# ESP01_ManualPushbutton.net
KiCad netlist of a schematic drawn in EAGLE
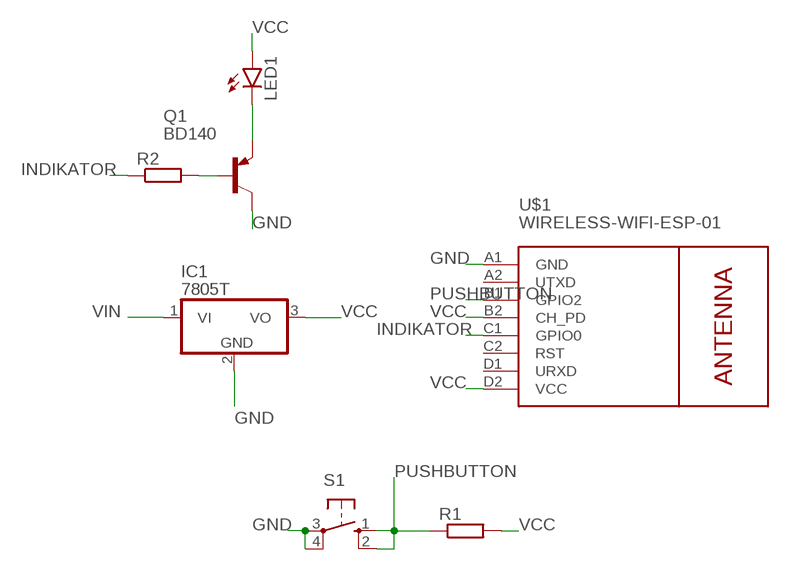
[diagram p0: schematic, sheet 1]

(export (version "E")
  (design (tool "Eeschema 10.0.6"))
  (components
    (comp (ref "IC1")
      (value "7805T")
      (footprint "eagle-import:TO220H")
      (libsource (lib "eagle-import") (part "78T05"))
    )
    (comp (ref "LED1")
      (value "LED5MM")
      (footprint "eagle-import:LED5MM")
      (libsource (lib "eagle-import") (part "LED5MM"))
    )
    (comp (ref "Q1")
      (value "BD140")
      (footprint "eagle-import:TO126")
      (libsource (lib "eagle-import") (part "BD140"))
    )
    (comp (ref "R1")
      (value "R-EU_0207/10")
      (footprint "eagle-import:0207_10")
      (libsource (lib "eagle-import") (part "R-EU_0207/10"))
    )
    (comp (ref "R2")
      (value "R-EU_0207/10")
      (footprint "eagle-import:0207_10")
      (libsource (lib "eagle-import") (part "R-EU_0207/10"))
    )
    (comp (ref "S1")
      (value "10-XX")
      (footprint "eagle-import:B3F-10XX")
      (fields (field (name "MPN") "B3F-1000"))
      (libsource (lib "eagle-import") (part "10-XX"))
    )
    (comp (ref "U$1")
      (value "WIRELESS-WIFI-ESP-01")
      (footprint "eagle-import:WIRELESS-WIFI-ESP-01")
      (libsource (lib "eagle-import") (part "WIRELESS-WIFI-ESP-01"))
    )
  )
  (nets
    (net (code "1") (name "/GND") (class "Default")
      (node (ref "IC1") (pin "2") (pinfunction "GND_2") (pintype "passive"))
      (node (ref "Q1") (pin "2") (pinfunction "C_2") (pintype "passive"))
      (node (ref "S1") (pin "3") (pinfunction "P_3") (pintype "passive"))
      (node (ref "S1") (pin "4") (pinfunction "P1_4") (pintype "passive"))
      (node (ref "U$1") (pin "A1") (pinfunction "GND_A1") (pintype "power_in"))
    )
    (net (code "2") (name "/INDIKATOR") (class "Default")
      (node (ref "R2") (pin "1") (pinfunction "1_1") (pintype "passive"))
      (node (ref "U$1") (pin "C1") (pinfunction "GPIO0_C1") (pintype "bidirectional"))
    )
    (net (code "3") (name "/PUSHBUTTON") (class "Default")
      (node (ref "R1") (pin "1") (pinfunction "1_1") (pintype "passive"))
      (node (ref "S1") (pin "1") (pinfunction "S_1") (pintype "passive"))
      (node (ref "S1") (pin "2") (pinfunction "S1_2") (pintype "passive"))
      (node (ref "U$1") (pin "B1") (pinfunction "GPIO2_B1") (pintype "bidirectional"))
    )
    (net (code "4") (name "/VCC") (class "Default")
      (node (ref "IC1") (pin "3") (pinfunction "VO_3") (pintype "passive"))
      (node (ref "LED1") (pin "A") (pinfunction "A_A") (pintype "passive"))
      (node (ref "R1") (pin "2") (pinfunction "2_2") (pintype "passive"))
      (node (ref "U$1") (pin "B2") (pinfunction "CH_PD_B2") (pintype "bidirectional"))
      (node (ref "U$1") (pin "D2") (pinfunction "VCC_D2") (pintype "power_in"))
    )
    (net (code "5") (name "/VIN") (class "Default")
      (node (ref "IC1") (pin "1") (pinfunction "VI_1") (pintype "input"))
    )
    (net (code "6") (name "Net-(LED1-C)") (class "Default")
      (node (ref "LED1") (pin "K") (pinfunction "C_K") (pintype "passive"))
      (node (ref "Q1") (pin "1") (pinfunction "E_1") (pintype "passive"))
    )
    (net (code "7") (name "Net-(Q1-B)") (class "Default")
      (node (ref "Q1") (pin "3") (pinfunction "B_3") (pintype "passive"))
      (node (ref "R2") (pin "2") (pinfunction "2_2") (pintype "passive"))
    )
    (net (code "8") (name "unconnected-(U$1-RST-PadC2)") (class "Default")
      (node (ref "U$1") (pin "C2") (pinfunction "RST_C2") (pintype "bidirectional"))
    )
    (net (code "9") (name "unconnected-(U$1-URXD-PadD1)") (class "Default")
      (node (ref "U$1") (pin "D1") (pinfunction "URXD_D1") (pintype "bidirectional"))
    )
    (net (code "10") (name "unconnected-(U$1-UTXD-PadA2)") (class "Default")
      (node (ref "U$1") (pin "A2") (pinfunction "UTXD_A2") (pintype "bidirectional"))
    )
  )
)
